# 01_BLBB_Power.net
KiCad netlist of a schematic drawn in Altium Designer
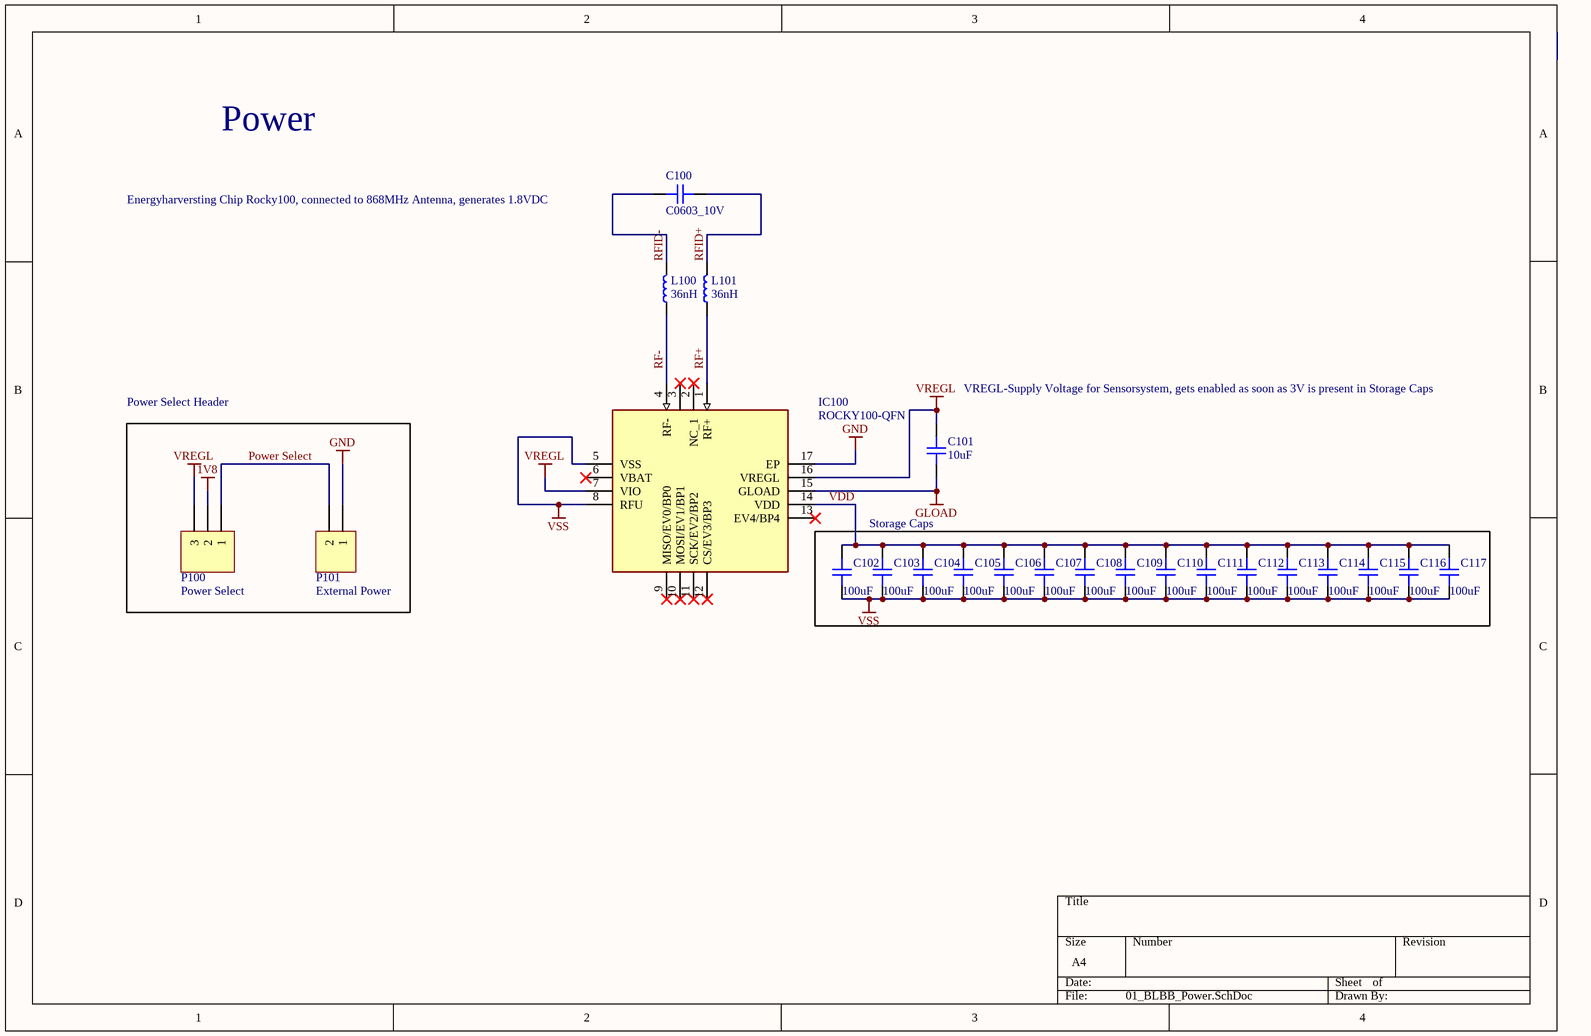
[diagram p0: 01_BLBB_Power.SchDoc]

(export (version "E")
  (design (tool "Eeschema 10.0.6"))
  (components
    (comp (ref "C100")
      (value "C0603_10V")
      (footprint "CAP_0603")
      (description "Capacitor SMD 0603 10V")
      (libsource (lib "Schematic-Lib-PhilsLab") (part "CAP_0603_10V"))
    )
    (comp (ref "C101")
      (value "10uF")
      (footprint "CAP_0603")
      (description "Capacitor SMD 0603 10V")
      (libsource (lib "Schematic-Lib-PhilsLab") (part "CAP_0603_10V"))
    )
    (comp (ref "C102")
      (value "100uF")
      (footprint "CAP_1206")
      (description "Capacitor SMD 1206 10V")
      (libsource (lib "Schematic-Lib-PhilsLab") (part "CAP_1206_10V"))
    )
    (comp (ref "C103")
      (value "100uF")
      (footprint "CAP_1206")
      (description "Capacitor SMD 1206 10V")
      (libsource (lib "Schematic-Lib-PhilsLab") (part "CAP_1206_10V"))
    )
    (comp (ref "C104")
      (value "100uF")
      (footprint "CAP_1206")
      (description "Capacitor SMD 1206 10V")
      (libsource (lib "Schematic-Lib-PhilsLab") (part "CAP_1206_10V"))
    )
    (comp (ref "C105")
      (value "100uF")
      (footprint "CAP_1206")
      (description "Capacitor SMD 1206 10V")
      (libsource (lib "Schematic-Lib-PhilsLab") (part "CAP_1206_10V"))
    )
    (comp (ref "C106")
      (value "100uF")
      (footprint "CAP_1206")
      (description "Capacitor SMD 1206 10V")
      (libsource (lib "Schematic-Lib-PhilsLab") (part "CAP_1206_10V"))
    )
    (comp (ref "C107")
      (value "100uF")
      (footprint "CAP_1206")
      (description "Capacitor SMD 1206 10V")
      (libsource (lib "Schematic-Lib-PhilsLab") (part "CAP_1206_10V"))
    )
    (comp (ref "C108")
      (value "100uF")
      (footprint "CAP_1206")
      (description "Capacitor SMD 1206 10V")
      (libsource (lib "Schematic-Lib-PhilsLab") (part "CAP_1206_10V"))
    )
    (comp (ref "C109")
      (value "100uF")
      (footprint "CAP_1206")
      (description "Capacitor SMD 1206 10V")
      (libsource (lib "Schematic-Lib-PhilsLab") (part "CAP_1206_10V"))
    )
    (comp (ref "C110")
      (value "100uF")
      (footprint "CAP_1206")
      (description "Capacitor SMD 1206 10V")
      (libsource (lib "Schematic-Lib-PhilsLab") (part "CAP_1206_10V"))
    )
    (comp (ref "C111")
      (value "100uF")
      (footprint "CAP_1206")
      (description "Capacitor SMD 1206 10V")
      (libsource (lib "Schematic-Lib-PhilsLab") (part "CAP_1206_10V"))
    )
    (comp (ref "C112")
      (value "100uF")
      (footprint "CAP_1206")
      (description "Capacitor SMD 1206 10V")
      (libsource (lib "Schematic-Lib-PhilsLab") (part "CAP_1206_10V"))
    )
    (comp (ref "C113")
      (value "100uF")
      (footprint "CAP_1206")
      (description "Capacitor SMD 1206 10V")
      (libsource (lib "Schematic-Lib-PhilsLab") (part "CAP_1206_10V"))
    )
    (comp (ref "C114")
      (value "100uF")
      (footprint "CAP_1206")
      (description "Capacitor SMD 1206 10V")
      (libsource (lib "Schematic-Lib-PhilsLab") (part "CAP_1206_10V"))
    )
    (comp (ref "C115")
      (value "100uF")
      (footprint "CAP_1206")
      (description "Capacitor SMD 1206 10V")
      (libsource (lib "Schematic-Lib-PhilsLab") (part "CAP_1206_10V"))
    )
    (comp (ref "C116")
      (value "100uF")
      (footprint "CAP_1206")
      (description "Capacitor SMD 1206 10V")
      (libsource (lib "Schematic-Lib-PhilsLab") (part "CAP_1206_10V"))
    )
    (comp (ref "C117")
      (value "100uF")
      (footprint "CAP_1206")
      (description "Capacitor SMD 1206 10V")
      (libsource (lib "Schematic-Lib-PhilsLab") (part "CAP_1206_10V"))
    )
    (comp (ref "IC100")
      (value "ROCKY100-QFN")
      (footprint "SamacSys:QFN65P400X400X80-17N-D")
      (description "Integrated Circuit")
      (libsource (lib "SamacSys") (part "ROCKY100-QFN"))
    )
    (comp (ref "L100")
      (value "36nH")
      (footprint "IND_0603")
      (description "Inductor SMD 0603")
      (libsource (lib "Schematic-Lib-PhilsLab") (part "IND_0603"))
    )
    (comp (ref "L101")
      (value "36nH")
      (footprint "IND_0603")
      (description "Inductor SMD 0603")
      (libsource (lib "Schematic-Lib-PhilsLab") (part "IND_0603"))
    )
    (comp (ref "P100")
      (value "Power Select")
      (footprint "HDR1X3")
      (description "Header, 3-Pin")
      (fields (field (name "PUBLISHER") "Altium Limited"))
      (libsource (lib "Miscellaneous Connectors") (part "Header 3"))
    )
    (comp (ref "P101")
      (value "External Power")
      (footprint "HDR1X2")
      (fields (field (name "PUBLISHER") "Altium Limited"))
      (libsource (lib "Miscellaneous Connectors") (part "Header 2"))
    )
  )
  (nets
    (net (code "1") (name "/Power Select") (class "Default")
      (node (ref "P100") (pin "1") (pinfunction "1_1") (pintype "passive"))
      (node (ref "P101") (pin "2") (pinfunction "2_2") (pintype "passive"))
    )
    (net (code "2") (name "/RF+") (class "Default")
      (node (ref "IC100") (pin "1") (pinfunction "RF+_1") (pintype "input"))
      (node (ref "L101") (pin "1") (pinfunction "1_1") (pintype "passive"))
    )
    (net (code "3") (name "/RF-") (class "Default")
      (node (ref "IC100") (pin "4") (pinfunction "RF-_4") (pintype "input"))
      (node (ref "L100") (pin "1") (pinfunction "1_1") (pintype "passive"))
    )
    (net (code "4") (name "/RFID+") (class "Default")
      (node (ref "C100") (pin "2") (pinfunction "2_2") (pintype "passive"))
      (node (ref "L101") (pin "2") (pinfunction "2_2") (pintype "passive"))
    )
    (net (code "5") (name "/RFID-") (class "Default")
      (node (ref "C100") (pin "1") (pinfunction "1_1") (pintype "passive"))
      (node (ref "L100") (pin "2") (pinfunction "2_2") (pintype "passive"))
    )
    (net (code "6") (name "/VDD") (class "Default")
      (node (ref "C102") (pin "2") (pinfunction "2_2") (pintype "passive"))
      (node (ref "C103") (pin "2") (pinfunction "2_2") (pintype "passive"))
      (node (ref "C104") (pin "2") (pinfunction "2_2") (pintype "passive"))
      (node (ref "C105") (pin "2") (pinfunction "2_2") (pintype "passive"))
      (node (ref "C106") (pin "2") (pinfunction "2_2") (pintype "passive"))
      (node (ref "C107") (pin "2") (pinfunction "2_2") (pintype "passive"))
      (node (ref "C108") (pin "2") (pinfunction "2_2") (pintype "passive"))
      (node (ref "C109") (pin "2") (pinfunction "2_2") (pintype "passive"))
      (node (ref "C110") (pin "2") (pinfunction "2_2") (pintype "passive"))
      (node (ref "C111") (pin "2") (pinfunction "2_2") (pintype "passive"))
      (node (ref "C112") (pin "2") (pinfunction "2_2") (pintype "passive"))
      (node (ref "C113") (pin "2") (pinfunction "2_2") (pintype "passive"))
      (node (ref "C114") (pin "2") (pinfunction "2_2") (pintype "passive"))
      (node (ref "C115") (pin "2") (pinfunction "2_2") (pintype "passive"))
      (node (ref "C116") (pin "2") (pinfunction "2_2") (pintype "passive"))
      (node (ref "C117") (pin "2") (pinfunction "2_2") (pintype "passive"))
      (node (ref "IC100") (pin "14") (pinfunction "VDD_14") (pintype "power_in"))
    )
    (net (code "7") (name "1V8") (class "Default")
      (node (ref "P100") (pin "2") (pinfunction "2_2") (pintype "passive"))
    )
    (net (code "8") (name "GLOAD") (class "Default")
      (node (ref "C101") (pin "1") (pinfunction "1_1") (pintype "passive"))
      (node (ref "IC100") (pin "15") (pinfunction "GLOAD_15") (pintype "power_in"))
    )
    (net (code "9") (name "GND") (class "Default")
      (node (ref "IC100") (pin "17") (pinfunction "EP_17") (pintype "power_in"))
      (node (ref "P101") (pin "1") (pinfunction "1_1") (pintype "passive"))
    )
    (net (code "10") (name "VREGL") (class "Default")
      (node (ref "C101") (pin "2") (pinfunction "2_2") (pintype "passive"))
      (node (ref "IC100") (pin "16") (pinfunction "VREGL_16") (pintype "power_in"))
      (node (ref "IC100") (pin "7") (pinfunction "VIO_7") (pintype "power_in"))
      (node (ref "P100") (pin "3") (pinfunction "3_3") (pintype "passive"))
    )
    (net (code "11") (name "VSS") (class "Default")
      (node (ref "C102") (pin "1") (pinfunction "1_1") (pintype "passive"))
      (node (ref "C103") (pin "1") (pinfunction "1_1") (pintype "passive"))
      (node (ref "C104") (pin "1") (pinfunction "1_1") (pintype "passive"))
      (node (ref "C105") (pin "1") (pinfunction "1_1") (pintype "passive"))
      (node (ref "C106") (pin "1") (pinfunction "1_1") (pintype "passive"))
      (node (ref "C107") (pin "1") (pinfunction "1_1") (pintype "passive"))
      (node (ref "C108") (pin "1") (pinfunction "1_1") (pintype "passive"))
      (node (ref "C109") (pin "1") (pinfunction "1_1") (pintype "passive"))
      (node (ref "C110") (pin "1") (pinfunction "1_1") (pintype "passive"))
      (node (ref "C111") (pin "1") (pinfunction "1_1") (pintype "passive"))
      (node (ref "C112") (pin "1") (pinfunction "1_1") (pintype "passive"))
      (node (ref "C113") (pin "1") (pinfunction "1_1") (pintype "passive"))
      (node (ref "C114") (pin "1") (pinfunction "1_1") (pintype "passive"))
      (node (ref "C115") (pin "1") (pinfunction "1_1") (pintype "passive"))
      (node (ref "C116") (pin "1") (pinfunction "1_1") (pintype "passive"))
      (node (ref "C117") (pin "1") (pinfunction "1_1") (pintype "passive"))
      (node (ref "IC100") (pin "5") (pinfunction "VSS_5") (pintype "power_in"))
      (node (ref "IC100") (pin "8") (pinfunction "RFU_8") (pintype "passive"))
    )
    (net (code "12") (name "unconnected-(IC100-CS{slash}EV3{slash}BP3-Pad12)") (class "Default")
      (node (ref "IC100") (pin "12") (pinfunction "CS/EV3/BP3_12") (pintype "passive+no_connect"))
    )
    (net (code "13") (name "unconnected-(IC100-EV4{slash}BP4-Pad13)") (class "Default")
      (node (ref "IC100") (pin "13") (pinfunction "EV4/BP4_13") (pintype "passive+no_connect"))
    )
    (net (code "14") (name "unconnected-(IC100-MISO{slash}EV0{slash}BP0-Pad9)") (class "Default")
      (node (ref "IC100") (pin "9") (pinfunction "MISO/EV0/BP0_9") (pintype "passive+no_connect"))
    )
    (net (code "15") (name "unconnected-(IC100-MOSI{slash}EV1{slash}BP1-Pad10)") (class "Default")
      (node (ref "IC100") (pin "10") (pinfunction "MOSI/EV1/BP1_10") (pintype "passive+no_connect"))
    )
    (net (code "16") (name "unconnected-(IC100-NC_1-Pad2)") (class "Default")
      (node (ref "IC100") (pin "2") (pinfunction "NC_1_2") (pintype "passive+no_connect"))
    )
    (net (code "17") (name "unconnected-(IC100-NC_2-Pad3)") (class "Default")
      (node (ref "IC100") (pin "3") (pinfunction "NC_2_3") (pintype "passive+no_connect"))
    )
    (net (code "18") (name "unconnected-(IC100-SCK{slash}EV2{slash}BP2-Pad11)") (class "Default")
      (node (ref "IC100") (pin "11") (pinfunction "SCK/EV2/BP2_11") (pintype "passive+no_connect"))
    )
    (net (code "19") (name "unconnected-(IC100-VBAT-Pad6)") (class "Default")
      (node (ref "IC100") (pin "6") (pinfunction "VBAT_6") (pintype "power_in+no_connect"))
    )
  )
)
